# V3.net
KiCad netlist of a schematic drawn in EasyEDA Pro
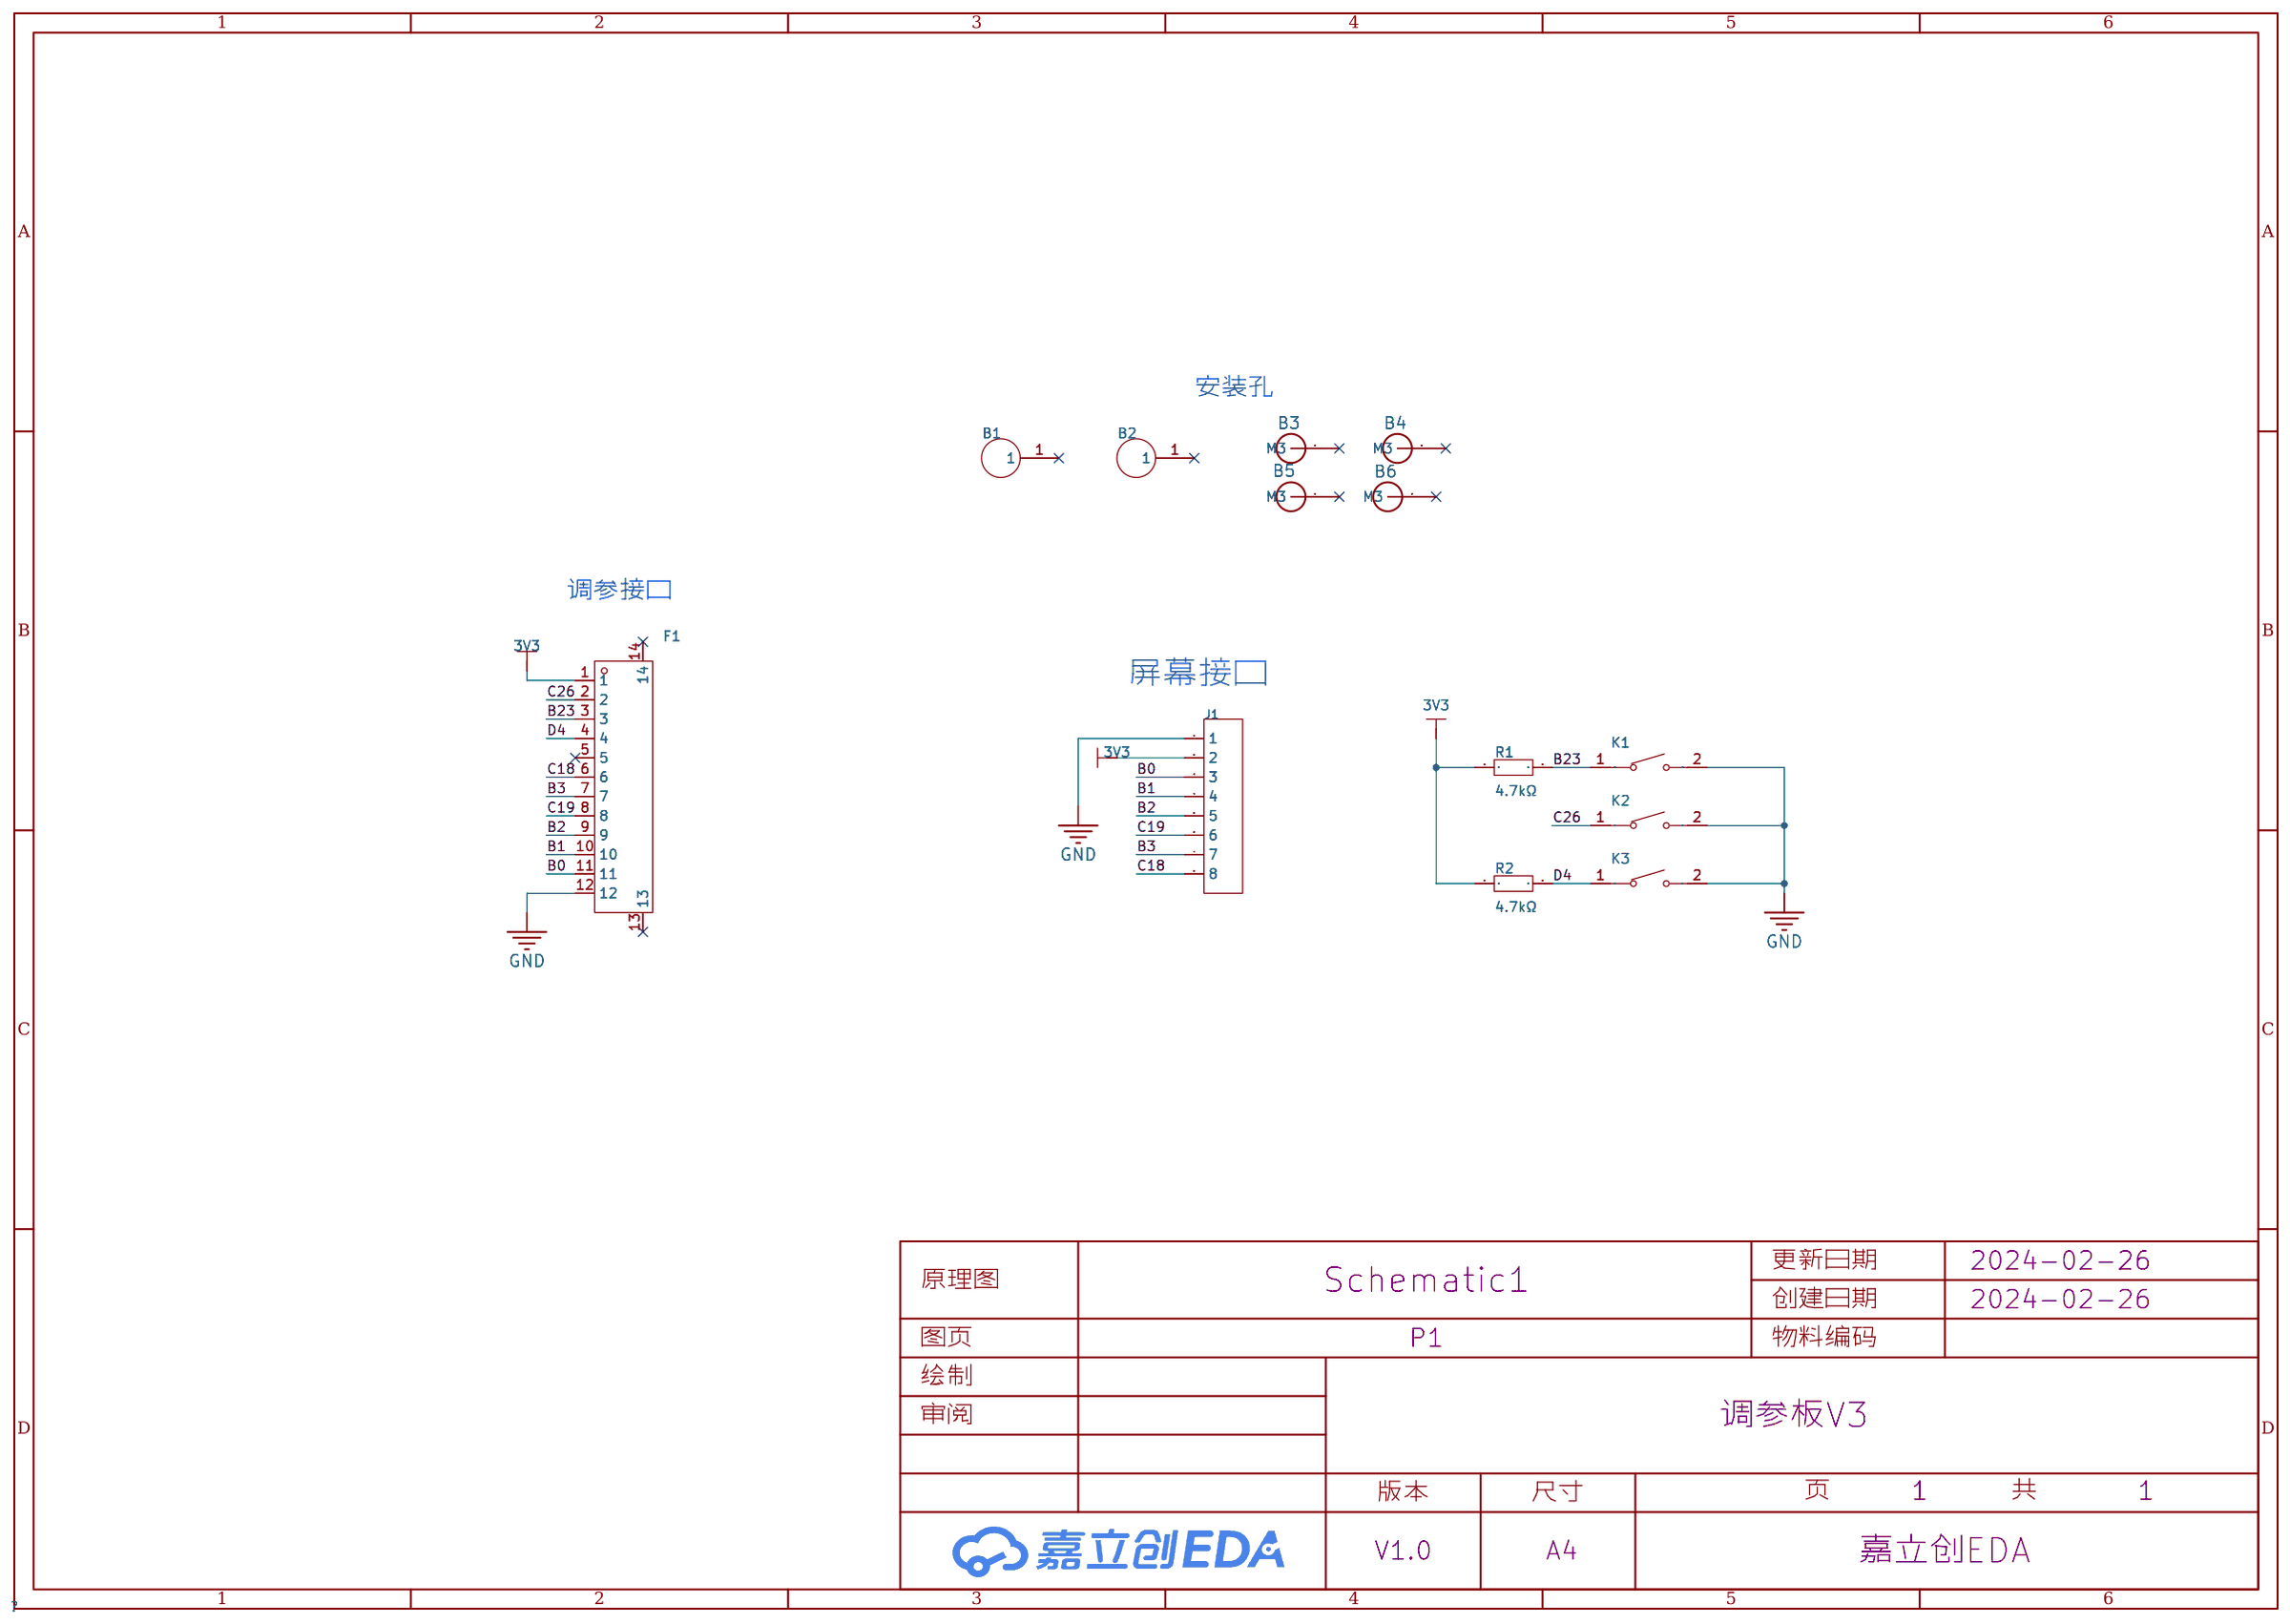
[diagram p0: schematic sheet]

(export (version "E")
  (design (tool "Eeschema 10.0.6"))
  (components
    (comp (ref "B1") (value "~") (footprint "easyedapro:M2") (libsource (lib "easyedapro") (part "M2")))
    (comp (ref "B2") (value "~") (footprint "easyedapro:M2") (libsource (lib "easyedapro") (part "M2")))
    (comp (ref "B3")
      (value "M3螺柱孔_JX")
      (footprint "easyedapro:M3")
      (libsource (lib "easyedapro") (part "M3螺柱孔_JX"))
    )
    (comp (ref "B4")
      (value "M3螺柱孔_JX")
      (footprint "easyedapro:M3")
      (libsource (lib "easyedapro") (part "M3螺柱孔_JX"))
    )
    (comp (ref "B5")
      (value "M3螺柱孔_JX")
      (footprint "easyedapro:M3")
      (libsource (lib "easyedapro") (part "M3螺柱孔_JX"))
    )
    (comp (ref "B6")
      (value "M3螺柱孔_JX")
      (footprint "easyedapro:M3")
      (libsource (lib "easyedapro") (part "M3螺柱孔_JX"))
    )
    (comp (ref "F1")
      (value "FPC-1.0FX-12PWCR-H20")
      (footprint "easyedapro:FPC-SMD_XUNPU_FPC-1.0FX-12PWCR-H20")
      (description "锁定特性:翻盖式;触点类型:下接;触点数量:12P;间距:1mm;安装类型:卧贴;")
      (fields (field (name "Manufacturer") "XUNPU(讯普)"))
      (libsource (lib "easyedapro") (part "FPC-1.0FX-12PWCR-H20"))
    )
    (comp (ref "J1")
      (value "~")
      (footprint "easyedapro:HDR-TH_8P-P2.54-V-F-1")
      (libsource (lib "easyedapro") (part "Header-Female-2.54_1x8"))
    )
    (comp (ref "K1")
      (value "TS665WS 250gf")
      (footprint "easyedapro:SW-SMD_L6.0-W6.0-LS6.6")
      (fields (field (name "Manufacturer") "SHOU HAN(首韩)"))
      (libsource (lib "easyedapro") (part "TS665WS 250GF"))
    )
    (comp (ref "K2")
      (value "TS665WS 250gf")
      (footprint "easyedapro:SW-SMD_L6.0-W6.0-LS6.6")
      (fields (field (name "Manufacturer") "SHOU HAN(首韩)"))
      (libsource (lib "easyedapro") (part "TS665WS 250GF"))
    )
    (comp (ref "K3")
      (value "TS665WS 250gf")
      (footprint "easyedapro:SW-SMD_L6.0-W6.0-LS6.6")
      (fields (field (name "Manufacturer") "SHOU HAN(首韩)"))
      (libsource (lib "easyedapro") (part "TS665WS 250GF"))
    )
    (comp (ref "R1")
      (value "4.7kΩ")
      (footprint "easyedapro:R0603")
      (description "电阻类型:厚膜电阻;阻值:4.7kΩ;精度:±1%;功率:100mW;最大工作电压:75V;温度系数:±100ppm/°C;")
      (fields
        (field (name "Manufacturer Part") "0603WAF4701T5E")
        (field (name "Manufacturer") "UNI-ROYAL(厚声)")
      )
      (libsource (lib "easyedapro") (part "0603WAF4701T5E"))
    )
    (comp (ref "R2")
      (value "4.7kΩ")
      (footprint "easyedapro:R0603")
      (description "电阻类型:厚膜电阻;阻值:4.7kΩ;精度:±1%;功率:100mW;最大工作电压:75V;温度系数:±100ppm/°C;")
      (fields
        (field (name "Manufacturer Part") "0603WAF4701T5E")
        (field (name "Manufacturer") "UNI-ROYAL(厚声)")
      )
      (libsource (lib "easyedapro") (part "0603WAF4701T5E"))
    )
  )
  (nets
    (net (code "1") (name "/B0") (class "Default")
      (node (ref "F1") (pin "11") (pinfunction "11_11") (pintype "unspecified"))
      (node (ref "J1") (pin "3") (pinfunction "3_3") (pintype "input"))
    )
    (net (code "2") (name "/B1") (class "Default")
      (node (ref "F1") (pin "10") (pinfunction "10_10") (pintype "unspecified"))
      (node (ref "J1") (pin "4") (pinfunction "4_4") (pintype "input"))
    )
    (net (code "3") (name "/B2") (class "Default")
      (node (ref "F1") (pin "9") (pinfunction "9_9") (pintype "unspecified"))
      (node (ref "J1") (pin "5") (pinfunction "5_5") (pintype "input"))
    )
    (net (code "4") (name "/B3") (class "Default")
      (node (ref "F1") (pin "7") (pinfunction "7_7") (pintype "unspecified"))
      (node (ref "J1") (pin "7") (pinfunction "7_7") (pintype "input"))
    )
    (net (code "5") (name "/B23") (class "Default")
      (node (ref "F1") (pin "3") (pinfunction "3_3") (pintype "unspecified"))
      (node (ref "K1") (pin "1") (pinfunction "A_1") (pintype "unspecified"))
      (node (ref "R1") (pin "2") (pinfunction "2_2") (pintype "input"))
    )
    (net (code "6") (name "/C18") (class "Default")
      (node (ref "F1") (pin "6") (pinfunction "6_6") (pintype "unspecified"))
      (node (ref "J1") (pin "8") (pinfunction "8_8") (pintype "input"))
    )
    (net (code "7") (name "/C19") (class "Default")
      (node (ref "F1") (pin "8") (pinfunction "8_8") (pintype "unspecified"))
      (node (ref "J1") (pin "6") (pinfunction "6_6") (pintype "input"))
    )
    (net (code "8") (name "/C26") (class "Default")
      (node (ref "F1") (pin "2") (pinfunction "2_2") (pintype "unspecified"))
      (node (ref "K2") (pin "1") (pinfunction "A_1") (pintype "unspecified"))
    )
    (net (code "9") (name "/D4") (class "Default")
      (node (ref "F1") (pin "4") (pinfunction "4_4") (pintype "unspecified"))
      (node (ref "K3") (pin "1") (pinfunction "A_1") (pintype "unspecified"))
      (node (ref "R2") (pin "2") (pinfunction "2_2") (pintype "input"))
    )
    (net (code "10") (name "3V3") (class "Default")
      (node (ref "F1") (pin "1") (pinfunction "1_1") (pintype "unspecified"))
      (node (ref "J1") (pin "2") (pinfunction "2_2") (pintype "input"))
      (node (ref "R1") (pin "1") (pinfunction "1_1") (pintype "input"))
      (node (ref "R2") (pin "1") (pinfunction "1_1") (pintype "input"))
    )
    (net (code "11") (name "GND") (class "Default")
      (node (ref "F1") (pin "12") (pinfunction "12_12") (pintype "unspecified"))
      (node (ref "J1") (pin "1") (pinfunction "1_1") (pintype "input"))
      (node (ref "K1") (pin "2") (pinfunction "B_2") (pintype "unspecified"))
      (node (ref "K2") (pin "2") (pinfunction "B_2") (pintype "unspecified"))
      (node (ref "K3") (pin "2") (pinfunction "B_2") (pintype "unspecified"))
    )
    (net (code "12") (name "unconnected-(B1-Pad1)") (class "Default")
      (node (ref "B1") (pin "1") (pinfunction "1_1") (pintype "input+no_connect"))
    )
    (net (code "13") (name "unconnected-(B2-Pad1)") (class "Default")
      (node (ref "B2") (pin "1") (pinfunction "1_1") (pintype "input+no_connect"))
    )
    (net (code "14") (name "unconnected-(B3-M3-Pad1)") (class "Default")
      (node (ref "B3") (pin "1") (pinfunction "M3_1") (pintype "input+no_connect"))
    )
    (net (code "15") (name "unconnected-(B4-M3-Pad1)") (class "Default")
      (node (ref "B4") (pin "1") (pinfunction "M3_1") (pintype "input+no_connect"))
    )
    (net (code "16") (name "unconnected-(B5-M3-Pad1)") (class "Default")
      (node (ref "B5") (pin "1") (pinfunction "M3_1") (pintype "input+no_connect"))
    )
    (net (code "17") (name "unconnected-(B6-M3-Pad1)") (class "Default")
      (node (ref "B6") (pin "1") (pinfunction "M3_1") (pintype "input+no_connect"))
    )
    (net (code "18") (name "unconnected-(F1-Pad5)") (class "Default")
      (node (ref "F1") (pin "5") (pinfunction "5_5") (pintype "unspecified+no_connect"))
    )
    (net (code "19") (name "unconnected-(F1-Pad13)") (class "Default")
      (node (ref "F1") (pin "13") (pinfunction "13_13") (pintype "unspecified+no_connect"))
    )
    (net (code "20") (name "unconnected-(F1-Pad14)") (class "Default")
      (node (ref "F1") (pin "14") (pinfunction "14_14") (pintype "unspecified+no_connect"))
    )
  )
)
